# ADC.net
KiCad netlist of a schematic drawn in Altium Designer
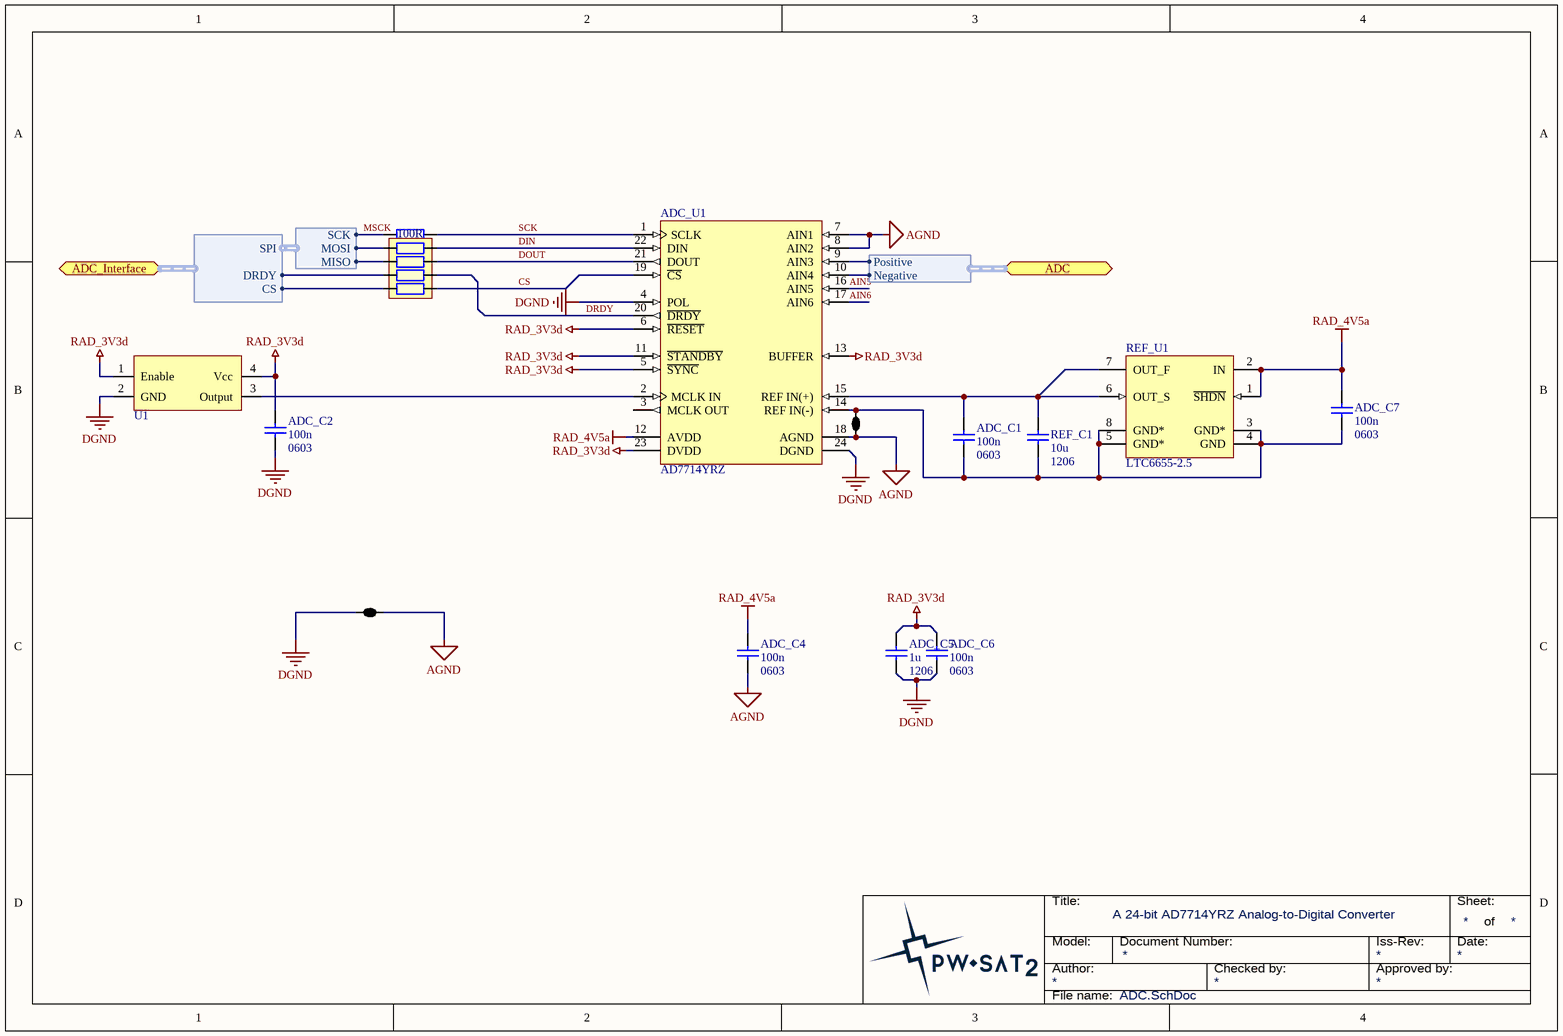
[diagram p0: ADC.SchDoc]

(export (version "E")
  (design (tool "Eeschema 10.0.6"))
  (components
    (comp (ref "ADC_C1")
      (value "100n")
      (footprint "SMD_Capacitor_0603")
      (description "Cap")
      (fields (field (name "PACKAGE") "0603"))
      (libsource (lib "capacitors") (part "Cap"))
    )
    (comp (ref "ADC_C2")
      (value "100n")
      (footprint "SMD_Capacitor_0603")
      (description "Cap")
      (fields (field (name "PACKAGE") "0603"))
      (libsource (lib "capacitors") (part "Cap"))
    )
    (comp (ref "ADC_C4")
      (value "100n")
      (footprint "SMD_Capacitor_0603")
      (description "Cap")
      (fields (field (name "PACKAGE") "0603"))
      (libsource (lib "capacitors") (part "Cap"))
    )
    (comp (ref "ADC_C5")
      (value "1u")
      (footprint "SMD_Capacitor_1206")
      (description "Cap")
      (fields (field (name "PACKAGE") "1206"))
      (libsource (lib "capacitors") (part "Cap"))
    )
    (comp (ref "ADC_C6")
      (value "100n")
      (footprint "SMD_Capacitor_0603")
      (description "Cap")
      (fields (field (name "PACKAGE") "0603"))
      (libsource (lib "capacitors") (part "Cap"))
    )
    (comp (ref "ADC_C7")
      (value "100n")
      (footprint "SMD_Capacitor_0603")
      (description "Cap")
      (fields (field (name "PACKAGE") "0603"))
      (libsource (lib "capacitors") (part "Cap"))
    )
    (comp (ref "ADC_J1")
      (value "2 way net tie junction")
      (footprint "2way_LP")
      (libsource (lib "") (part "2way_1"))
    )
    (comp (ref "ADC_J2")
      (value "2 way net tie junction")
      (footprint "2way_LP")
      (libsource (lib "NetTieLib") (part "2way"))
    )
    (comp (ref "ADC_R1")
      (value "100R")
      (footprint "SMD_Resistor_0603")
      (libsource (lib "resistors") (part "Res"))
    )
    (comp (ref "ADC_R2")
      (value "YC124-JR-072K2L")
      (footprint "SMD_RESISTOR_ARRAY_YC124")
      (description "RESISTOR ARRAY, 4 x 0402")
      (libsource (lib "resistors") (part "YC124-JR-072K2L"))
    )
    (comp (ref "ADC_U1")
      (value "AD7714YRZ")
      (footprint "TSSOP-24-RU-24-N")
      (fields (field (name "GENERIC PART NUMBER") "AD7714") (field (name "MANUFACTURER") "Analog Devices"))
      (libsource (lib "microcircuits") (part "AD7714YRZ"))
    )
    (comp (ref "REF_C1")
      (value "10u")
      (footprint "SMD_Capacitor_1206")
      (description "Cap")
      (fields (field (name "PACKAGE") "1206"))
      (libsource (lib "capacitors") (part "Cap"))
    )
    (comp (ref "REF_U1")
      (value "LTC6655-2.5")
      (footprint "MSOP-8")
      (description "0.25ppm Noise, Low Drift  Precision References")
      (libsource (lib "microcircuits") (part "LTC6655-2.5"))
    )
    (comp (ref "U1")
      (value "Ceramic Crystal")
      (footprint "2.0 x 2.5 mm")
      (description "Ceramic Crystal 1 MHz, A-Grade 25 ppm/deg")
      (libsource (lib "crystal") (part "ISM95-3351AH-1.0000"))
    )
  )
  (nets
    (net (code "6") (name "/AIN5") (class "Default")
      (node (ref "ADC_U1") (pin "16") (pinfunction "AIN5_16") (pintype "input"))
    )
    (net (code "7") (name "/AIN6") (class "Default")
      (node (ref "ADC_U1") (pin "17") (pinfunction "AIN6_17") (pintype "input"))
    )
    (net (code "8") (name "/CS") (class "Default")
      (node (ref "ADC_R2") (pin "4") (pinfunction "4_4") (pintype "passive"))
      (node (ref "ADC_U1") (pin "19") (pinfunction "~{CS}_19") (pintype "input"))
    )
    (net (code "9") (name "/DIN") (class "Default")
      (node (ref "ADC_R2") (pin "1") (pinfunction "1_1") (pintype "passive"))
      (node (ref "ADC_U1") (pin "22") (pinfunction "DIN_22") (pintype "input"))
    )
    (net (code "10") (name "/DOUT") (class "Default")
      (node (ref "ADC_R2") (pin "2") (pinfunction "2_2") (pintype "passive"))
      (node (ref "ADC_U1") (pin "21") (pinfunction "DOUT_21") (pintype "output"))
    )
    (net (code "11") (name "/DRDY") (class "Default")
      (node (ref "ADC_R2") (pin "3") (pinfunction "3_3") (pintype "passive"))
      (node (ref "ADC_U1") (pin "20") (pinfunction "~{DRDY}_20") (pintype "output"))
    )
    (net (code "12") (name "/MISO") (class "Default")
      (node (ref "ADC_R2") (pin "7") (pinfunction "7_7") (pintype "passive"))
    )
    (net (code "13") (name "/MOSI") (class "Default")
      (node (ref "ADC_R2") (pin "8") (pinfunction "8_8") (pintype "passive"))
    )
    (net (code "14") (name "/MSCK") (class "Default")
      (node (ref "ADC_R1") (pin "1") (pinfunction "1_1") (pintype "passive"))
    )
    (net (code "15") (name "/Negative") (class "Default")
      (node (ref "ADC_U1") (pin "10") (pinfunction "AIN4_10") (pintype "input"))
    )
    (net (code "16") (name "/Positive") (class "Default")
      (node (ref "ADC_U1") (pin "9") (pinfunction "AIN3_9") (pintype "input"))
    )
    (net (code "17") (name "/SCK") (class "Default")
      (node (ref "ADC_R1") (pin "2") (pinfunction "2_2") (pintype "passive"))
      (node (ref "ADC_U1") (pin "1") (pinfunction "SCLK_1") (pintype "input"))
    )
    (net (code "20") (name "AGND") (class "Default")
      (node (ref "ADC_C4") (pin "2") (pinfunction "2_2") (pintype "passive"))
      (node (ref "ADC_J1") (pin "1") (pinfunction "1_1") (pintype "passive"))
      (node (ref "ADC_J2") (pin "1") (pinfunction "1_1") (pintype "passive"))
      (node (ref "ADC_U1") (pin "18") (pinfunction "AGND_18") (pintype "power_in"))
      (node (ref "ADC_U1") (pin "7") (pinfunction "AIN1_7") (pintype "input"))
      (node (ref "ADC_U1") (pin "8") (pinfunction "AIN2_8") (pintype "input"))
    )
    (net (code "21") (name "DGND") (class "Default")
      (node (ref "ADC_C2") (pin "2") (pinfunction "2_2") (pintype "passive"))
      (node (ref "ADC_C5") (pin "2") (pinfunction "2_2") (pintype "passive"))
      (node (ref "ADC_C6") (pin "2") (pinfunction "2_2") (pintype "passive"))
      (node (ref "ADC_J1") (pin "2") (pinfunction "2_2") (pintype "passive"))
      (node (ref "ADC_U1") (pin "24") (pinfunction "DGND_24") (pintype "power_in"))
      (node (ref "ADC_U1") (pin "4") (pinfunction "POL_4") (pintype "input"))
      (node (ref "U1") (pin "2") (pinfunction "GND_2") (pintype "passive"))
    )
    (net (code "22") (name "Net-(ADC_U1-MCLK_IN)") (class "Default")
      (node (ref "ADC_U1") (pin "2") (pinfunction "MCLK_IN_2") (pintype "input"))
      (node (ref "U1") (pin "3") (pinfunction "Output_3") (pintype "passive"))
    )
    (net (code "23") (name "Net-(ADC_U1-REF_IN(+))") (class "Default")
      (node (ref "ADC_C1") (pin "1") (pinfunction "1_1") (pintype "passive"))
      (node (ref "ADC_U1") (pin "15") (pinfunction "REF_IN(+)_15") (pintype "input"))
      (node (ref "REF_C1") (pin "1") (pinfunction "1_1") (pintype "passive"))
      (node (ref "REF_U1") (pin "6") (pinfunction "OUT_S_6") (pintype "input"))
      (node (ref "REF_U1") (pin "7") (pinfunction "OUT_F_7") (pintype "power_in"))
    )
    (net (code "24") (name "Net-(ADC_U1-REF_IN(-))") (class "Default")
      (node (ref "ADC_C1") (pin "2") (pinfunction "2_2") (pintype "passive"))
      (node (ref "ADC_C7") (pin "2") (pinfunction "2_2") (pintype "passive"))
      (node (ref "ADC_J2") (pin "2") (pinfunction "2_2") (pintype "passive"))
      (node (ref "ADC_U1") (pin "14") (pinfunction "REF_IN(-)_14") (pintype "input"))
      (node (ref "REF_C1") (pin "2") (pinfunction "2_2") (pintype "passive"))
      (node (ref "REF_U1") (pin "3") (pinfunction "GND*_3") (pintype "power_in"))
      (node (ref "REF_U1") (pin "4") (pinfunction "GND_4") (pintype "power_in"))
      (node (ref "REF_U1") (pin "5") (pinfunction "GND*_5") (pintype "power_in"))
      (node (ref "REF_U1") (pin "8") (pinfunction "GND*_8") (pintype "power_in"))
    )
    (net (code "25") (name "RAD_3V3d") (class "Default")
      (node (ref "ADC_C2") (pin "1") (pinfunction "1_1") (pintype "passive"))
      (node (ref "ADC_C5") (pin "1") (pinfunction "1_1") (pintype "passive"))
      (node (ref "ADC_C6") (pin "1") (pinfunction "1_1") (pintype "passive"))
      (node (ref "ADC_U1") (pin "11") (pinfunction "~{STANDBY}_11") (pintype "input"))
      (node (ref "ADC_U1") (pin "13") (pinfunction "BUFFER_13") (pintype "input"))
      (node (ref "ADC_U1") (pin "23") (pinfunction "DVDD_23") (pintype "power_in"))
      (node (ref "ADC_U1") (pin "5") (pinfunction "~{SYNC}_5") (pintype "input"))
      (node (ref "ADC_U1") (pin "6") (pinfunction "~{RESET}_6") (pintype "input"))
      (node (ref "U1") (pin "1") (pinfunction "Enable_1") (pintype "passive"))
      (node (ref "U1") (pin "4") (pinfunction "Vcc_4") (pintype "passive"))
    )
    (net (code "26") (name "RAD_4V5a") (class "Default")
      (node (ref "ADC_C4") (pin "1") (pinfunction "1_1") (pintype "passive"))
      (node (ref "ADC_C7") (pin "1") (pinfunction "1_1") (pintype "passive"))
      (node (ref "ADC_U1") (pin "12") (pinfunction "AVDD_12") (pintype "power_in"))
      (node (ref "REF_U1") (pin "1") (pinfunction "~{SHDN}_1") (pintype "input"))
      (node (ref "REF_U1") (pin "2") (pinfunction "IN_2") (pintype "power_in"))
    )
    (net (code "27") (name "unconnected-(ADC_R2-Pad5)") (class "Default")
      (node (ref "ADC_R2") (pin "5") (pinfunction "5_5") (pintype "passive"))
    )
    (net (code "28") (name "unconnected-(ADC_R2-Pad6)") (class "Default")
      (node (ref "ADC_R2") (pin "6") (pinfunction "6_6") (pintype "passive"))
    )
    (net (code "29") (name "unconnected-(ADC_U1-MCLK_OUT-Pad3)") (class "Default")
      (node (ref "ADC_U1") (pin "3") (pinfunction "MCLK_OUT_3") (pintype "output"))
    )
  )
)
